# 301_Photodiode_Board.net
KiCad netlist of a schematic drawn in EAGLE
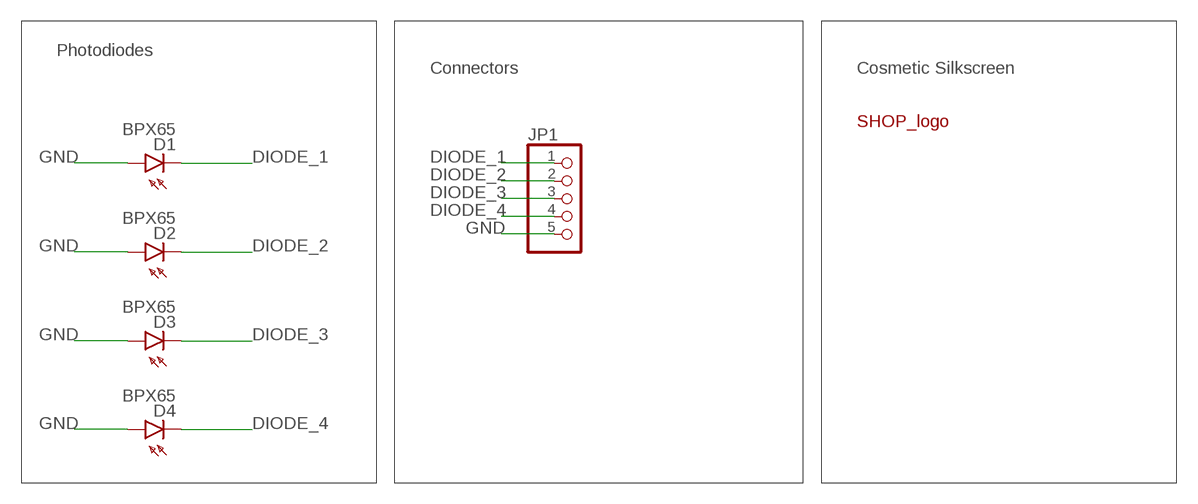
[diagram p0: schematic, sheet 1]

(export (version "E")
  (design (tool "Eeschema 10.0.6"))
  (components
    (comp (ref "D1")
      (value "BPX65")
      (footprint "eagle-import:BPX65")
      (fields (field (name "MPN") "BPX65."))
      (libsource (lib "eagle-import") (part "BPX65"))
    )
    (comp (ref "D2")
      (value "BPX65")
      (footprint "eagle-import:BPX65")
      (fields (field (name "MPN") "BPX65."))
      (libsource (lib "eagle-import") (part "BPX65"))
    )
    (comp (ref "D3")
      (value "BPX65")
      (footprint "eagle-import:BPX65")
      (fields (field (name "MPN") "BPX65."))
      (libsource (lib "eagle-import") (part "BPX65"))
    )
    (comp (ref "D4")
      (value "BPX65")
      (footprint "eagle-import:BPX65")
      (fields (field (name "MPN") "BPX65."))
      (libsource (lib "eagle-import") (part "BPX65"))
    )
    (comp (ref "JP1")
      (value "PINHD-1X5")
      (footprint "eagle-import:1X05")
      (libsource (lib "eagle-import") (part "PINHD-1X5"))
    )
    (comp (ref "U$2")
      (value "COUGAR_LOGO_LARGE")
      (footprint "eagle-import:LRG_COUGAR")
      (libsource (lib "eagle-import") (part "COUGAR_LOGO_LARGE"))
    )
  )
  (nets
    (net (code "1") (name "/DIODE_1") (class "Default")
      (node (ref "D1") (pin "K") (pinfunction "C_K") (pintype "passive"))
      (node (ref "JP1") (pin "1") (pinfunction "1_1") (pintype "passive"))
    )
    (net (code "2") (name "/DIODE_2") (class "Default")
      (node (ref "D2") (pin "K") (pinfunction "C_K") (pintype "passive"))
      (node (ref "JP1") (pin "2") (pinfunction "2_2") (pintype "passive"))
    )
    (net (code "3") (name "/DIODE_3") (class "Default")
      (node (ref "D3") (pin "K") (pinfunction "C_K") (pintype "passive"))
      (node (ref "JP1") (pin "3") (pinfunction "3_3") (pintype "passive"))
    )
    (net (code "4") (name "/DIODE_4") (class "Default")
      (node (ref "D4") (pin "K") (pinfunction "C_K") (pintype "passive"))
      (node (ref "JP1") (pin "4") (pinfunction "4_4") (pintype "passive"))
    )
    (net (code "5") (name "/GND") (class "Default")
      (node (ref "D1") (pin "A") (pinfunction "A_A") (pintype "passive"))
      (node (ref "D2") (pin "A") (pinfunction "A_A") (pintype "passive"))
      (node (ref "D3") (pin "A") (pinfunction "A_A") (pintype "passive"))
      (node (ref "D4") (pin "A") (pinfunction "A_A") (pintype "passive"))
      (node (ref "JP1") (pin "5") (pinfunction "5_5") (pintype "passive"))
    )
  )
)
